# ArduinoParser.net
KiCad netlist of a schematic drawn in EAGLE
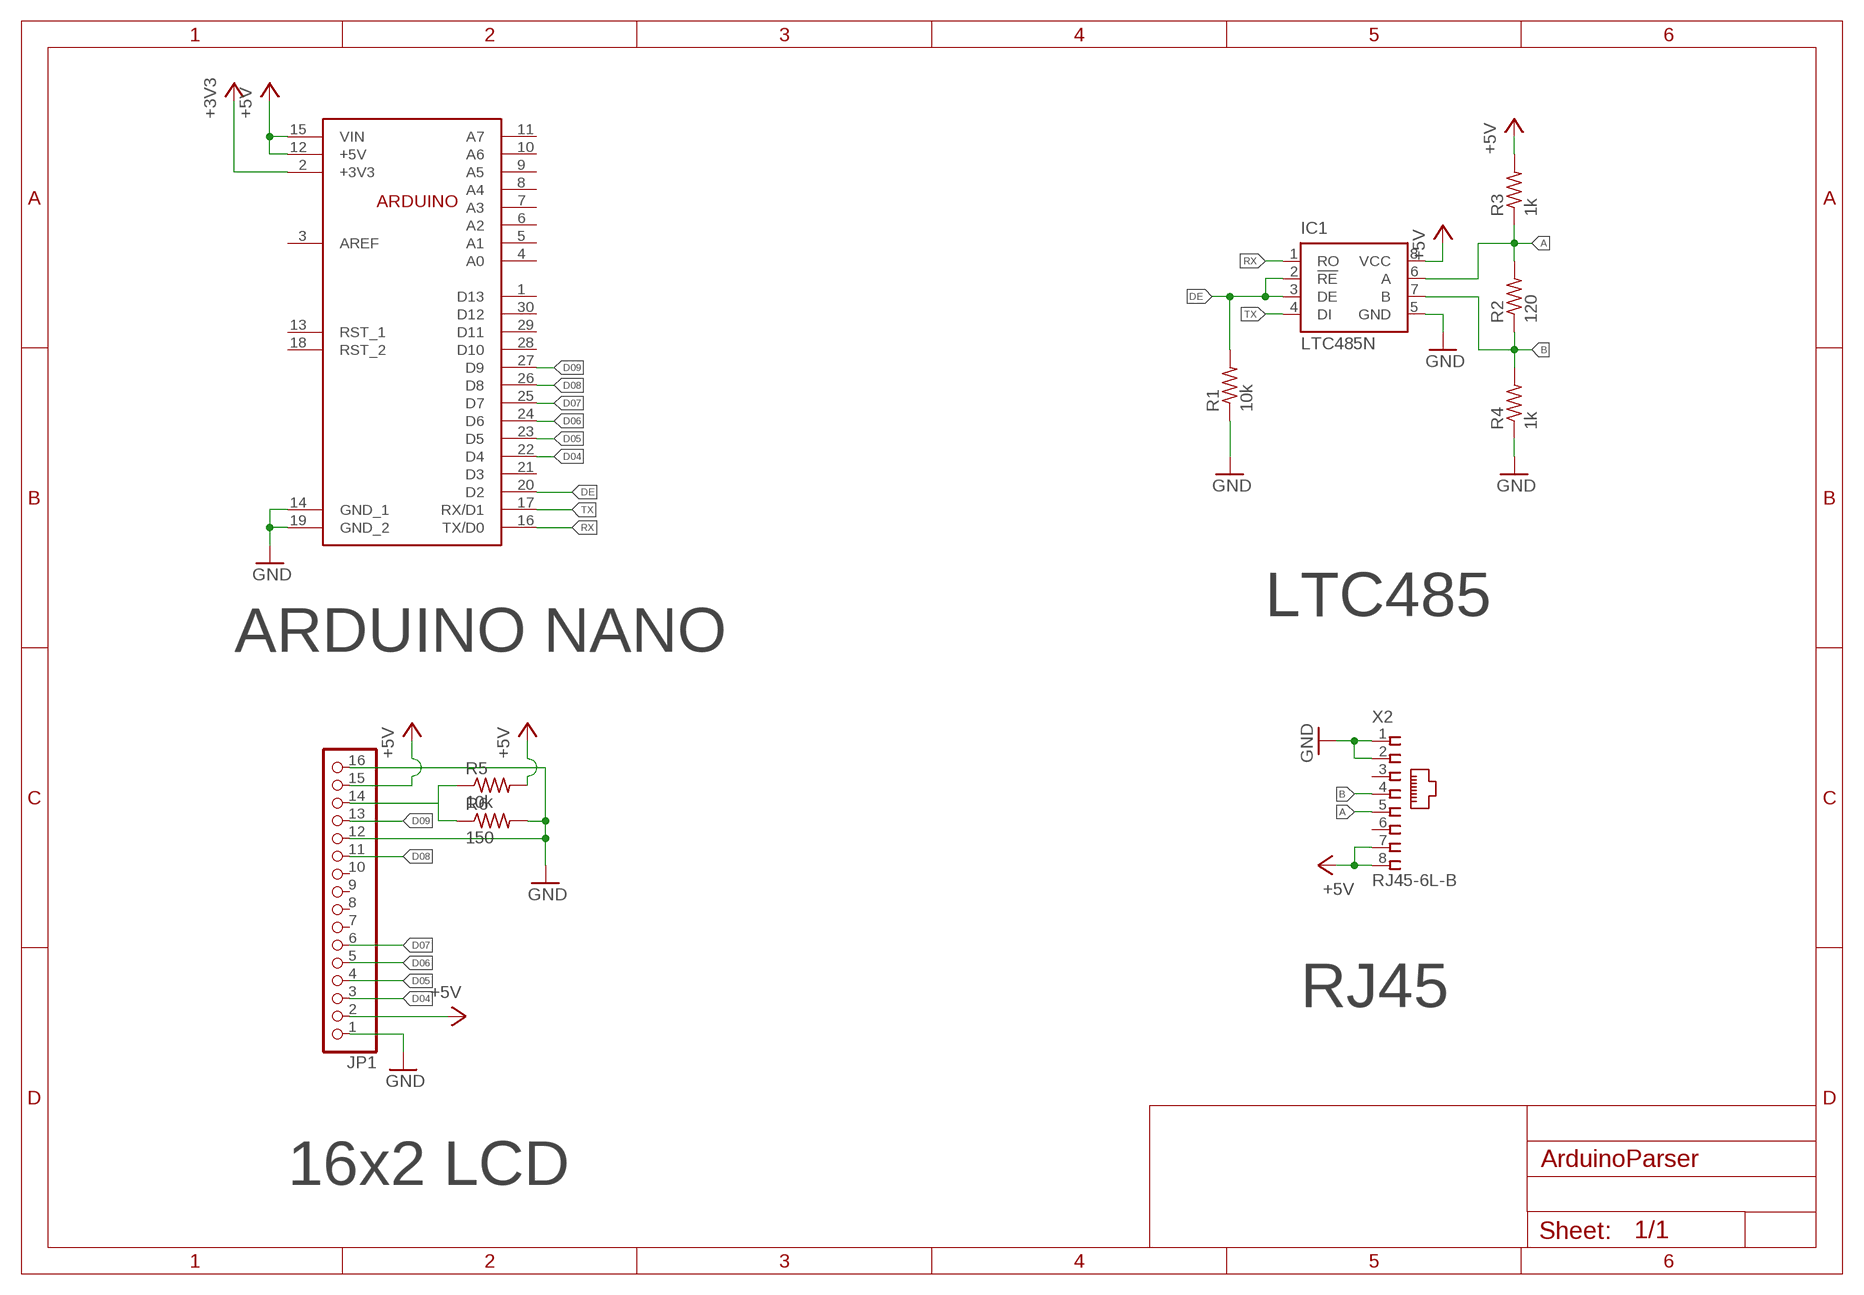
[diagram p0: schematic, sheet 1]

(export (version "E")
  (design (tool "Eeschema 10.0.6"))
  (components
    (comp (ref "IC1")
      (value "LTC485N")
      (footprint "eagle-import:DIL08")
      (libsource (lib "eagle-import") (part "LTC485N"))
    )
    (comp (ref "JP1")
      (value "PINHD-1X16")
      (footprint "eagle-import:1X16")
      (libsource (lib "eagle-import") (part "PINHD-1X16"))
    )
    (comp (ref "R1")
      (value "10k")
      (footprint "eagle-import:0204_7")
      (libsource (lib "eagle-import") (part "R-US_0204/7"))
    )
    (comp (ref "R2")
      (value "120")
      (footprint "eagle-import:0204_7")
      (libsource (lib "eagle-import") (part "R-US_0204/7"))
    )
    (comp (ref "R3")
      (value "1k")
      (footprint "eagle-import:0204_7")
      (libsource (lib "eagle-import") (part "R-US_0204/7"))
    )
    (comp (ref "R4")
      (value "1k")
      (footprint "eagle-import:0204_7")
      (libsource (lib "eagle-import") (part "R-US_0204/7"))
    )
    (comp (ref "R5")
      (value "10k")
      (footprint "eagle-import:0204_7")
      (libsource (lib "eagle-import") (part "R-US_0204/7"))
    )
    (comp (ref "R6")
      (value "150")
      (footprint "eagle-import:0204_7")
      (libsource (lib "eagle-import") (part "R-US_0204/7"))
    )
    (comp (ref "U$2")
      (value "ARDUINONANO")
      (footprint "eagle-import:ARDUINO")
      (libsource (lib "eagle-import") (part "ARDUINONANO"))
    )
    (comp (ref "X2")
      (value "RJ45-6L-B")
      (footprint "eagle-import:RJ45-NO-SHIELD")
      (libsource (lib "eagle-import") (part "RJ45-6L-B"))
    )
  )
  (nets
    (net (code "1") (name "+3V3") (class "Default")
      (node (ref "U$2") (pin "2") (pinfunction "+3V3_2") (pintype "bidirectional"))
    )
    (net (code "2") (name "+5V") (class "Default")
      (node (ref "IC1") (pin "8") (pinfunction "VCC_8") (pintype "input"))
      (node (ref "JP1") (pin "15") (pinfunction "15_15") (pintype "passive"))
      (node (ref "JP1") (pin "2") (pinfunction "2_2") (pintype "passive"))
      (node (ref "R3") (pin "2") (pinfunction "2_2") (pintype "passive"))
      (node (ref "R5") (pin "2") (pinfunction "2_2") (pintype "passive"))
      (node (ref "U$2") (pin "12") (pinfunction "+5V_12") (pintype "bidirectional"))
      (node (ref "U$2") (pin "15") (pinfunction "VIN_15") (pintype "bidirectional"))
      (node (ref "X2") (pin "7") (pinfunction "7_7") (pintype "passive"))
      (node (ref "X2") (pin "8") (pinfunction "8_8") (pintype "passive"))
    )
    (net (code "3") (name "A") (class "Default")
      (node (ref "IC1") (pin "6") (pinfunction "A_6") (pintype "bidirectional"))
      (node (ref "R2") (pin "2") (pinfunction "2_2") (pintype "passive"))
      (node (ref "R3") (pin "1") (pinfunction "1_1") (pintype "passive"))
      (node (ref "X2") (pin "5") (pinfunction "5_5") (pintype "passive"))
    )
    (net (code "4") (name "B") (class "Default")
      (node (ref "IC1") (pin "7") (pinfunction "B_7") (pintype "bidirectional"))
      (node (ref "R2") (pin "1") (pinfunction "1_1") (pintype "passive"))
      (node (ref "R4") (pin "2") (pinfunction "2_2") (pintype "passive"))
      (node (ref "X2") (pin "4") (pinfunction "4_4") (pintype "passive"))
    )
    (net (code "5") (name "D04") (class "Default")
      (node (ref "JP1") (pin "3") (pinfunction "3_3") (pintype "passive"))
      (node (ref "U$2") (pin "22") (pinfunction "D4_22") (pintype "bidirectional"))
    )
    (net (code "6") (name "D05") (class "Default")
      (node (ref "JP1") (pin "4") (pinfunction "4_4") (pintype "passive"))
      (node (ref "U$2") (pin "23") (pinfunction "D5_23") (pintype "bidirectional"))
    )
    (net (code "7") (name "D06") (class "Default")
      (node (ref "JP1") (pin "5") (pinfunction "5_5") (pintype "passive"))
      (node (ref "U$2") (pin "24") (pinfunction "D6_24") (pintype "bidirectional"))
    )
    (net (code "8") (name "D07") (class "Default")
      (node (ref "JP1") (pin "6") (pinfunction "6_6") (pintype "passive"))
      (node (ref "U$2") (pin "25") (pinfunction "D7_25") (pintype "bidirectional"))
    )
    (net (code "9") (name "D08") (class "Default")
      (node (ref "JP1") (pin "11") (pinfunction "11_11") (pintype "passive"))
      (node (ref "U$2") (pin "26") (pinfunction "D8_26") (pintype "bidirectional"))
    )
    (net (code "10") (name "D09") (class "Default")
      (node (ref "JP1") (pin "13") (pinfunction "13_13") (pintype "passive"))
      (node (ref "U$2") (pin "27") (pinfunction "D9_27") (pintype "bidirectional"))
    )
    (net (code "11") (name "DE") (class "Default")
      (node (ref "IC1") (pin "2") (pinfunction "~{RE}_2") (pintype "input"))
      (node (ref "IC1") (pin "3") (pinfunction "DE_3") (pintype "input"))
      (node (ref "R1") (pin "2") (pinfunction "2_2") (pintype "passive"))
      (node (ref "U$2") (pin "20") (pinfunction "D2_20") (pintype "bidirectional"))
    )
    (net (code "12") (name "GND") (class "Default")
      (node (ref "IC1") (pin "5") (pinfunction "GND_5") (pintype "input"))
      (node (ref "JP1") (pin "1") (pinfunction "1_1") (pintype "passive"))
      (node (ref "JP1") (pin "12") (pinfunction "12_12") (pintype "passive"))
      (node (ref "JP1") (pin "16") (pinfunction "16_16") (pintype "passive"))
      (node (ref "R1") (pin "1") (pinfunction "1_1") (pintype "passive"))
      (node (ref "R4") (pin "1") (pinfunction "1_1") (pintype "passive"))
      (node (ref "R6") (pin "2") (pinfunction "2_2") (pintype "passive"))
      (node (ref "U$2") (pin "14") (pinfunction "GND_1_14") (pintype "bidirectional"))
      (node (ref "U$2") (pin "19") (pinfunction "GND_2_19") (pintype "bidirectional"))
      (node (ref "X2") (pin "1") (pinfunction "1_1") (pintype "passive"))
      (node (ref "X2") (pin "2") (pinfunction "2_2") (pintype "passive"))
    )
    (net (code "13") (name "Net-(JP1-Pad14)") (class "Default")
      (node (ref "JP1") (pin "14") (pinfunction "14_14") (pintype "passive"))
      (node (ref "R5") (pin "1") (pinfunction "1_1") (pintype "passive"))
      (node (ref "R6") (pin "1") (pinfunction "1_1") (pintype "passive"))
    )
    (net (code "14") (name "RX") (class "Default")
      (node (ref "IC1") (pin "1") (pinfunction "RO_1") (pintype "output"))
      (node (ref "U$2") (pin "16") (pinfunction "TX/D0_16") (pintype "bidirectional"))
    )
    (net (code "15") (name "TX") (class "Default")
      (node (ref "IC1") (pin "4") (pinfunction "DI_4") (pintype "input"))
      (node (ref "U$2") (pin "17") (pinfunction "RX/D1_17") (pintype "bidirectional"))
    )
    (net (code "16") (name "unconnected-(JP1-Pad7)") (class "Default")
      (node (ref "JP1") (pin "7") (pinfunction "7_7") (pintype "passive"))
    )
    (net (code "17") (name "unconnected-(JP1-Pad8)") (class "Default")
      (node (ref "JP1") (pin "8") (pinfunction "8_8") (pintype "passive"))
    )
    (net (code "18") (name "unconnected-(JP1-Pad9)") (class "Default")
      (node (ref "JP1") (pin "9") (pinfunction "9_9") (pintype "passive"))
    )
    (net (code "19") (name "unconnected-(JP1-Pad10)") (class "Default")
      (node (ref "JP1") (pin "10") (pinfunction "10_10") (pintype "passive"))
    )
    (net (code "20") (name "unconnected-(U$2-A0-Pad4)") (class "Default")
      (node (ref "U$2") (pin "4") (pinfunction "A0_4") (pintype "bidirectional"))
    )
    (net (code "21") (name "unconnected-(U$2-A1-Pad5)") (class "Default")
      (node (ref "U$2") (pin "5") (pinfunction "A1_5") (pintype "bidirectional"))
    )
    (net (code "22") (name "unconnected-(U$2-A2-Pad6)") (class "Default")
      (node (ref "U$2") (pin "6") (pinfunction "A2_6") (pintype "bidirectional"))
    )
    (net (code "23") (name "unconnected-(U$2-A3-Pad7)") (class "Default")
      (node (ref "U$2") (pin "7") (pinfunction "A3_7") (pintype "bidirectional"))
    )
    (net (code "24") (name "unconnected-(U$2-A4-Pad8)") (class "Default")
      (node (ref "U$2") (pin "8") (pinfunction "A4_8") (pintype "bidirectional"))
    )
    (net (code "25") (name "unconnected-(U$2-A5-Pad9)") (class "Default")
      (node (ref "U$2") (pin "9") (pinfunction "A5_9") (pintype "bidirectional"))
    )
    (net (code "26") (name "unconnected-(U$2-A6-Pad10)") (class "Default")
      (node (ref "U$2") (pin "10") (pinfunction "A6_10") (pintype "bidirectional"))
    )
    (net (code "27") (name "unconnected-(U$2-A7-Pad11)") (class "Default")
      (node (ref "U$2") (pin "11") (pinfunction "A7_11") (pintype "bidirectional"))
    )
    (net (code "28") (name "unconnected-(U$2-AREF-Pad3)") (class "Default")
      (node (ref "U$2") (pin "3") (pinfunction "AREF_3") (pintype "bidirectional"))
    )
    (net (code "29") (name "unconnected-(U$2-D3-Pad21)") (class "Default")
      (node (ref "U$2") (pin "21") (pinfunction "D3_21") (pintype "bidirectional"))
    )
    (net (code "30") (name "unconnected-(U$2-D10-Pad28)") (class "Default")
      (node (ref "U$2") (pin "28") (pinfunction "D10_28") (pintype "bidirectional"))
    )
    (net (code "31") (name "unconnected-(U$2-D11-Pad29)") (class "Default")
      (node (ref "U$2") (pin "29") (pinfunction "D11_29") (pintype "bidirectional"))
    )
    (net (code "32") (name "unconnected-(U$2-D12-Pad30)") (class "Default")
      (node (ref "U$2") (pin "30") (pinfunction "D12_30") (pintype "bidirectional"))
    )
    (net (code "33") (name "unconnected-(U$2-D13-Pad1)") (class "Default")
      (node (ref "U$2") (pin "1") (pinfunction "D13_1") (pintype "bidirectional"))
    )
    (net (code "34") (name "unconnected-(U$2-RST_1-Pad13)") (class "Default")
      (node (ref "U$2") (pin "13") (pinfunction "RST_1_13") (pintype "bidirectional"))
    )
    (net (code "35") (name "unconnected-(U$2-RST_2-Pad18)") (class "Default")
      (node (ref "U$2") (pin "18") (pinfunction "RST_2_18") (pintype "bidirectional"))
    )
    (net (code "36") (name "unconnected-(X2-Pad3)") (class "Default")
      (node (ref "X2") (pin "3") (pinfunction "3_3") (pintype "passive"))
    )
    (net (code "37") (name "unconnected-(X2-Pad6)") (class "Default")
      (node (ref "X2") (pin "6") (pinfunction "6_6") (pintype "passive"))
    )
  )
)
